# MDBT42Q_testboard.net
KiCad netlist of a schematic drawn in EAGLE
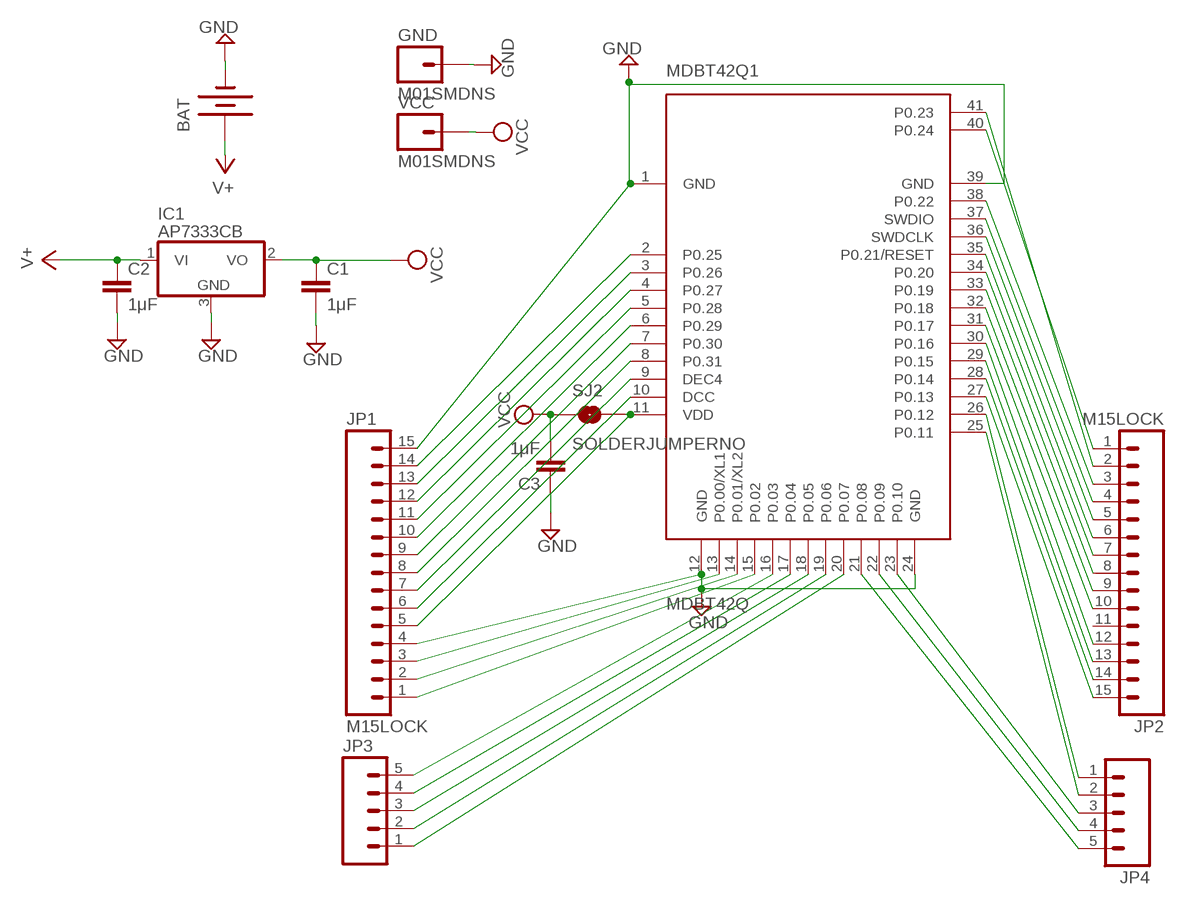
[diagram p0: schematic, sheet 1]

(export (version "E")
  (design (tool "Eeschema 10.0.6"))
  (components
    (comp (ref "BAT")
      (value "BATTERYFOB")
      (footprint "eagle-import:BATTERY_20MM_PTH_COMPACT")
      (libsource (lib "eagle-import") (part "BATTERYFOB"))
    )
    (comp (ref "C1")
      (value "1μF")
      (footprint "eagle-import:0603-CAP")
      (libsource (lib "eagle-import") (part "CAP0603-CAP"))
    )
    (comp (ref "C2")
      (value "1μF")
      (footprint "eagle-import:0603-CAP")
      (libsource (lib "eagle-import") (part "CAP0603-CAP"))
    )
    (comp (ref "C3")
      (value "1μF")
      (footprint "eagle-import:0603-CAP")
      (libsource (lib "eagle-import") (part "CAP0603-CAP"))
    )
    (comp (ref "GND")
      (value "M01SMDNS")
      (footprint "eagle-import:1X01NS")
      (libsource (lib "eagle-import") (part "M01SMDNS"))
    )
    (comp (ref "IC1")
      (value "AP7333CB")
      (footprint "eagle-import:SOT23")
      (libsource (lib "eagle-import") (part "AP7333CB"))
    )
    (comp (ref "JP1")
      (value "M15LOCK")
      (footprint "eagle-import:1X15_LOCK")
      (libsource (lib "eagle-import") (part "M15LOCK"))
    )
    (comp (ref "JP2")
      (value "M15LOCK")
      (footprint "eagle-import:1X15_LOCK")
      (libsource (lib "eagle-import") (part "M15LOCK"))
    )
    (comp (ref "JP3")
      (value "M05LOCK")
      (footprint "eagle-import:1X05_LOCK")
      (libsource (lib "eagle-import") (part "M05LOCK"))
    )
    (comp (ref "JP4")
      (value "M05LOCK")
      (footprint "eagle-import:1X05_LOCK")
      (libsource (lib "eagle-import") (part "M05LOCK"))
    )
    (comp (ref "MDBT42Q1")
      (value "MDBT42Q")
      (footprint "eagle-import:MDBT42Q")
      (libsource (lib "eagle-import") (part "MDBT42Q"))
    )
    (comp (ref "SJ2")
      (value "SOLDERJUMPERNO")
      (footprint "eagle-import:SJ_2S-NO")
      (libsource (lib "eagle-import") (part "SOLDERJUMPERNO"))
    )
    (comp (ref "VCC")
      (value "M01SMDNS")
      (footprint "eagle-import:1X01NS")
      (libsource (lib "eagle-import") (part "M01SMDNS"))
    )
  )
  (nets
    (net (code "1") (name "GND") (class "Default")
      (node (ref "BAT") (pin "2") (pinfunction "-_2") (pintype "power_in"))
      (node (ref "C1") (pin "2") (pinfunction "2_2") (pintype "passive"))
      (node (ref "C2") (pin "2") (pinfunction "2_2") (pintype "passive"))
      (node (ref "C3") (pin "1") (pinfunction "1_1") (pintype "passive"))
      (node (ref "GND") (pin "1") (pinfunction "1_1") (pintype "passive"))
      (node (ref "IC1") (pin "3") (pinfunction "GND_3") (pintype "passive"))
      (node (ref "JP1") (pin "15") (pinfunction "15_15") (pintype "passive"))
      (node (ref "JP1") (pin "4") (pinfunction "4_4") (pintype "passive"))
      (node (ref "MDBT42Q1") (pin "1") (pinfunction "GND_1") (pintype "bidirectional"))
      (node (ref "MDBT42Q1") (pin "12") (pinfunction "GND_12") (pintype "bidirectional"))
      (node (ref "MDBT42Q1") (pin "24") (pinfunction "GND_24") (pintype "bidirectional"))
      (node (ref "MDBT42Q1") (pin "39") (pinfunction "GND_39") (pintype "bidirectional"))
    )
    (net (code "2") (name "Net-(MDBT42Q1-DCC)") (class "Default")
      (node (ref "JP1") (pin "6") (pinfunction "6_6") (pintype "passive"))
      (node (ref "MDBT42Q1") (pin "10") (pinfunction "DCC_10") (pintype "bidirectional"))
    )
    (net (code "3") (name "Net-(MDBT42Q1-DEC4)") (class "Default")
      (node (ref "JP1") (pin "7") (pinfunction "7_7") (pintype "passive"))
      (node (ref "MDBT42Q1") (pin "9") (pinfunction "DEC4_9") (pintype "bidirectional"))
    )
    (net (code "4") (name "Net-(MDBT42Q1-P0.00{slash}XL1)") (class "Default")
      (node (ref "JP1") (pin "3") (pinfunction "3_3") (pintype "passive"))
      (node (ref "MDBT42Q1") (pin "13") (pinfunction "P0.00/XL1_13") (pintype "bidirectional"))
    )
    (net (code "5") (name "Net-(MDBT42Q1-P0.01{slash}XL2)") (class "Default")
      (node (ref "JP1") (pin "2") (pinfunction "2_2") (pintype "passive"))
      (node (ref "MDBT42Q1") (pin "14") (pinfunction "P0.01/XL2_14") (pintype "bidirectional"))
    )
    (net (code "6") (name "Net-(MDBT42Q1-P0.02)") (class "Default")
      (node (ref "JP1") (pin "1") (pinfunction "1_1") (pintype "passive"))
      (node (ref "MDBT42Q1") (pin "15") (pinfunction "P0.02_15") (pintype "bidirectional"))
    )
    (net (code "7") (name "Net-(MDBT42Q1-P0.03)") (class "Default")
      (node (ref "JP3") (pin "5") (pinfunction "5_5") (pintype "passive"))
      (node (ref "MDBT42Q1") (pin "16") (pinfunction "P0.03_16") (pintype "bidirectional"))
    )
    (net (code "8") (name "Net-(MDBT42Q1-P0.04)") (class "Default")
      (node (ref "JP3") (pin "4") (pinfunction "4_4") (pintype "passive"))
      (node (ref "MDBT42Q1") (pin "17") (pinfunction "P0.04_17") (pintype "bidirectional"))
    )
    (net (code "9") (name "Net-(MDBT42Q1-P0.05)") (class "Default")
      (node (ref "JP3") (pin "3") (pinfunction "3_3") (pintype "passive"))
      (node (ref "MDBT42Q1") (pin "18") (pinfunction "P0.05_18") (pintype "bidirectional"))
    )
    (net (code "10") (name "Net-(MDBT42Q1-P0.06)") (class "Default")
      (node (ref "JP3") (pin "2") (pinfunction "2_2") (pintype "passive"))
      (node (ref "MDBT42Q1") (pin "19") (pinfunction "P0.06_19") (pintype "bidirectional"))
    )
    (net (code "11") (name "Net-(MDBT42Q1-P0.07)") (class "Default")
      (node (ref "JP3") (pin "1") (pinfunction "1_1") (pintype "passive"))
      (node (ref "MDBT42Q1") (pin "20") (pinfunction "P0.07_20") (pintype "bidirectional"))
    )
    (net (code "12") (name "Net-(MDBT42Q1-P0.08)") (class "Default")
      (node (ref "JP4") (pin "5") (pinfunction "5_5") (pintype "passive"))
      (node (ref "MDBT42Q1") (pin "21") (pinfunction "P0.08_21") (pintype "bidirectional"))
    )
    (net (code "13") (name "Net-(MDBT42Q1-P0.09)") (class "Default")
      (node (ref "JP4") (pin "4") (pinfunction "4_4") (pintype "passive"))
      (node (ref "MDBT42Q1") (pin "22") (pinfunction "P0.09_22") (pintype "bidirectional"))
    )
    (net (code "14") (name "Net-(MDBT42Q1-P0.10)") (class "Default")
      (node (ref "JP4") (pin "3") (pinfunction "3_3") (pintype "passive"))
      (node (ref "MDBT42Q1") (pin "23") (pinfunction "P0.10_23") (pintype "bidirectional"))
    )
    (net (code "15") (name "Net-(MDBT42Q1-P0.11)") (class "Default")
      (node (ref "JP4") (pin "2") (pinfunction "2_2") (pintype "passive"))
      (node (ref "MDBT42Q1") (pin "25") (pinfunction "P0.11_25") (pintype "bidirectional"))
    )
    (net (code "16") (name "Net-(MDBT42Q1-P0.12)") (class "Default")
      (node (ref "JP4") (pin "1") (pinfunction "1_1") (pintype "passive"))
      (node (ref "MDBT42Q1") (pin "26") (pinfunction "P0.12_26") (pintype "bidirectional"))
    )
    (net (code "17") (name "Net-(MDBT42Q1-P0.13)") (class "Default")
      (node (ref "JP2") (pin "15") (pinfunction "15_15") (pintype "passive"))
      (node (ref "MDBT42Q1") (pin "27") (pinfunction "P0.13_27") (pintype "bidirectional"))
    )
    (net (code "18") (name "Net-(MDBT42Q1-P0.14)") (class "Default")
      (node (ref "JP2") (pin "14") (pinfunction "14_14") (pintype "passive"))
      (node (ref "MDBT42Q1") (pin "28") (pinfunction "P0.14_28") (pintype "bidirectional"))
    )
    (net (code "19") (name "Net-(MDBT42Q1-P0.15)") (class "Default")
      (node (ref "JP2") (pin "13") (pinfunction "13_13") (pintype "passive"))
      (node (ref "MDBT42Q1") (pin "29") (pinfunction "P0.15_29") (pintype "bidirectional"))
    )
    (net (code "20") (name "Net-(MDBT42Q1-P0.16)") (class "Default")
      (node (ref "JP2") (pin "12") (pinfunction "12_12") (pintype "passive"))
      (node (ref "MDBT42Q1") (pin "30") (pinfunction "P0.16_30") (pintype "bidirectional"))
    )
    (net (code "21") (name "Net-(MDBT42Q1-P0.17)") (class "Default")
      (node (ref "JP2") (pin "10") (pinfunction "10_10") (pintype "passive"))
      (node (ref "MDBT42Q1") (pin "31") (pinfunction "P0.17_31") (pintype "bidirectional"))
    )
    (net (code "22") (name "Net-(MDBT42Q1-P0.18)") (class "Default")
      (node (ref "JP2") (pin "9") (pinfunction "9_9") (pintype "passive"))
      (node (ref "MDBT42Q1") (pin "32") (pinfunction "P0.18_32") (pintype "bidirectional"))
    )
    (net (code "23") (name "Net-(MDBT42Q1-P0.19)") (class "Default")
      (node (ref "JP2") (pin "8") (pinfunction "8_8") (pintype "passive"))
      (node (ref "MDBT42Q1") (pin "33") (pinfunction "P0.19_33") (pintype "bidirectional"))
    )
    (net (code "24") (name "Net-(MDBT42Q1-P0.20)") (class "Default")
      (node (ref "JP2") (pin "7") (pinfunction "7_7") (pintype "passive"))
      (node (ref "MDBT42Q1") (pin "34") (pinfunction "P0.20_34") (pintype "bidirectional"))
    )
    (net (code "25") (name "Net-(MDBT42Q1-P0.21{slash}RESET)") (class "Default")
      (node (ref "JP2") (pin "6") (pinfunction "6_6") (pintype "passive"))
      (node (ref "MDBT42Q1") (pin "35") (pinfunction "P0.21/RESET_35") (pintype "bidirectional"))
    )
    (net (code "26") (name "Net-(MDBT42Q1-P0.22)") (class "Default")
      (node (ref "JP2") (pin "3") (pinfunction "3_3") (pintype "passive"))
      (node (ref "MDBT42Q1") (pin "38") (pinfunction "P0.22_38") (pintype "bidirectional"))
    )
    (net (code "27") (name "Net-(MDBT42Q1-P0.23)") (class "Default")
      (node (ref "JP2") (pin "2") (pinfunction "2_2") (pintype "passive"))
      (node (ref "MDBT42Q1") (pin "41") (pinfunction "P0.23_41") (pintype "bidirectional"))
    )
    (net (code "28") (name "Net-(MDBT42Q1-P0.24)") (class "Default")
      (node (ref "JP2") (pin "1") (pinfunction "1_1") (pintype "passive"))
      (node (ref "MDBT42Q1") (pin "40") (pinfunction "P0.24_40") (pintype "bidirectional"))
    )
    (net (code "29") (name "Net-(MDBT42Q1-P0.25)") (class "Default")
      (node (ref "JP1") (pin "14") (pinfunction "14_14") (pintype "passive"))
      (node (ref "MDBT42Q1") (pin "2") (pinfunction "P0.25_2") (pintype "bidirectional"))
    )
    (net (code "30") (name "Net-(MDBT42Q1-P0.26)") (class "Default")
      (node (ref "JP1") (pin "13") (pinfunction "13_13") (pintype "passive"))
      (node (ref "MDBT42Q1") (pin "3") (pinfunction "P0.26_3") (pintype "bidirectional"))
    )
    (net (code "31") (name "Net-(MDBT42Q1-P0.27)") (class "Default")
      (node (ref "JP1") (pin "12") (pinfunction "12_12") (pintype "passive"))
      (node (ref "MDBT42Q1") (pin "4") (pinfunction "P0.27_4") (pintype "bidirectional"))
    )
    (net (code "32") (name "Net-(MDBT42Q1-P0.28)") (class "Default")
      (node (ref "JP1") (pin "11") (pinfunction "11_11") (pintype "passive"))
      (node (ref "MDBT42Q1") (pin "5") (pinfunction "P0.28_5") (pintype "bidirectional"))
    )
    (net (code "33") (name "Net-(MDBT42Q1-P0.29)") (class "Default")
      (node (ref "JP1") (pin "10") (pinfunction "10_10") (pintype "passive"))
      (node (ref "MDBT42Q1") (pin "6") (pinfunction "P0.29_6") (pintype "bidirectional"))
    )
    (net (code "34") (name "Net-(MDBT42Q1-P0.30)") (class "Default")
      (node (ref "JP1") (pin "9") (pinfunction "9_9") (pintype "passive"))
      (node (ref "MDBT42Q1") (pin "7") (pinfunction "P0.30_7") (pintype "bidirectional"))
    )
    (net (code "35") (name "Net-(MDBT42Q1-P0.31)") (class "Default")
      (node (ref "JP1") (pin "8") (pinfunction "8_8") (pintype "passive"))
      (node (ref "MDBT42Q1") (pin "8") (pinfunction "P0.31_8") (pintype "bidirectional"))
    )
    (net (code "36") (name "Net-(MDBT42Q1-SWDCLK)") (class "Default")
      (node (ref "JP2") (pin "5") (pinfunction "5_5") (pintype "passive"))
      (node (ref "MDBT42Q1") (pin "36") (pinfunction "SWDCLK_36") (pintype "bidirectional"))
    )
    (net (code "37") (name "Net-(MDBT42Q1-SWDIO)") (class "Default")
      (node (ref "JP2") (pin "4") (pinfunction "4_4") (pintype "passive"))
      (node (ref "MDBT42Q1") (pin "37") (pinfunction "SWDIO_37") (pintype "bidirectional"))
    )
    (net (code "38") (name "Net-(MDBT42Q1-VDD)") (class "Default")
      (node (ref "JP1") (pin "5") (pinfunction "5_5") (pintype "passive"))
      (node (ref "MDBT42Q1") (pin "11") (pinfunction "VDD_11") (pintype "bidirectional"))
      (node (ref "SJ2") (pin "2") (pinfunction "2_2") (pintype "passive"))
    )
    (net (code "39") (name "V+") (class "Default")
      (node (ref "BAT") (pin "1") (pinfunction "+_1") (pintype "power_in"))
      (node (ref "C2") (pin "1") (pinfunction "1_1") (pintype "passive"))
      (node (ref "IC1") (pin "1") (pinfunction "VI_1") (pintype "input"))
    )
    (net (code "40") (name "VCC") (class "Default")
      (node (ref "C1") (pin "1") (pinfunction "1_1") (pintype "passive"))
      (node (ref "C3") (pin "2") (pinfunction "2_2") (pintype "passive"))
      (node (ref "IC1") (pin "2") (pinfunction "VO_2") (pintype "passive"))
      (node (ref "SJ2") (pin "1") (pinfunction "1_1") (pintype "passive"))
      (node (ref "VCC") (pin "1") (pinfunction "1_1") (pintype "passive"))
    )
    (net (code "41") (name "unconnected-(JP2-Pad11)") (class "Default")
      (node (ref "JP2") (pin "11") (pinfunction "11_11") (pintype "passive"))
    )
  )
)
